# Sheet2.net
KiCad netlist of a schematic drawn in Altium Designer
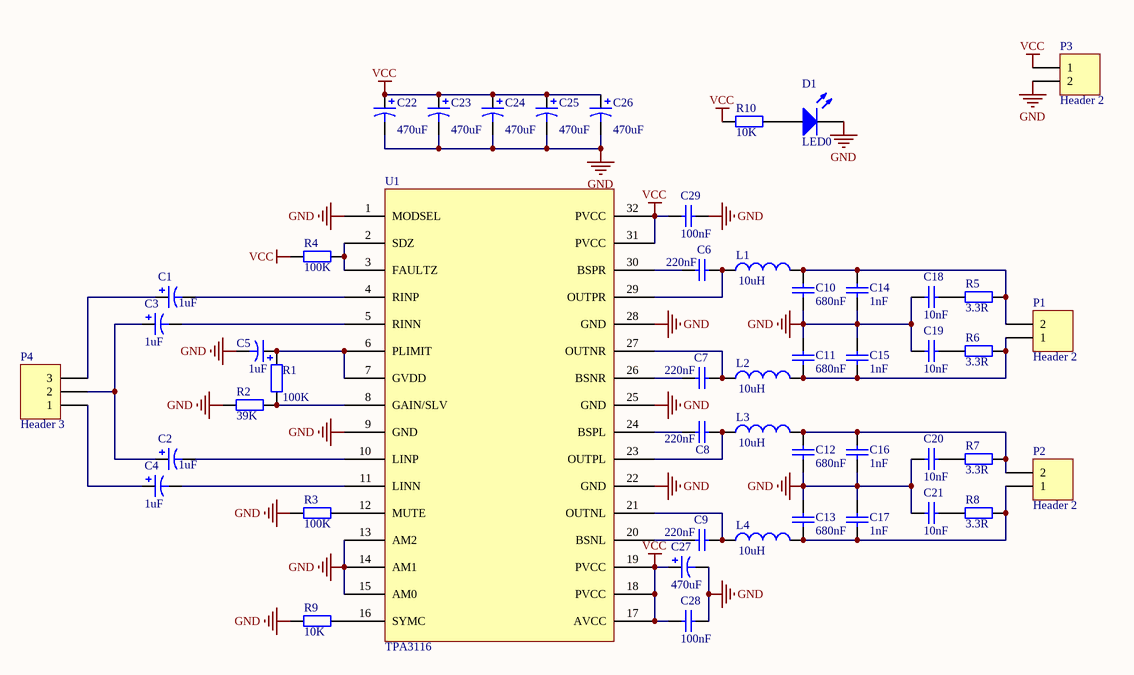
[diagram p0: Sheet2.SchDoc]

(export (version "E")
  (design (tool "Eeschema 10.0.6"))
  (components
    (comp (ref "C1")
      (value "1uF")
      (footprint "C0603")
      (description "Polarized Capacitor (Radial)")
      (fields (field (name "Comment") "Cap Pol1") (field (name "PUBLISHER") "Altium Limited"))
      (libsource (lib "Miscellaneous Devices") (part "Cap Pol1"))
    )
    (comp (ref "C2")
      (value "1uF")
      (footprint "C0603")
      (description "Polarized Capacitor (Radial)")
      (fields (field (name "Comment") "Cap Pol1") (field (name "PUBLISHER") "Altium Limited"))
      (libsource (lib "Miscellaneous Devices") (part "Cap Pol1"))
    )
    (comp (ref "C3")
      (value "1uF")
      (footprint "C0603")
      (description "Polarized Capacitor (Radial)")
      (fields (field (name "Comment") "Cap Pol1") (field (name "PUBLISHER") "Altium Limited"))
      (libsource (lib "Miscellaneous Devices") (part "Cap Pol1"))
    )
    (comp (ref "C4")
      (value "1uF")
      (footprint "C0603")
      (description "Polarized Capacitor (Radial)")
      (fields (field (name "Comment") "Cap Pol1") (field (name "PUBLISHER") "Altium Limited"))
      (libsource (lib "Miscellaneous Devices") (part "Cap Pol1"))
    )
    (comp (ref "C5")
      (value "1uF")
      (footprint "C0603")
      (description "Polarized Capacitor (Radial)")
      (fields (field (name "Comment") "Cap Pol1") (field (name "PUBLISHER") "Altium Limited"))
      (libsource (lib "Miscellaneous Devices") (part "Cap Pol1"))
    )
    (comp (ref "C6")
      (value "220nF")
      (footprint "C0805")
      (description "Capacitor")
      (fields (field (name "Comment") "Cap") (field (name "PUBLISHER") "Altium Limited"))
      (libsource (lib "Miscellaneous Devices") (part "Cap"))
    )
    (comp (ref "C7")
      (value "220nF")
      (footprint "C0805")
      (description "Capacitor")
      (fields (field (name "Comment") "Cap") (field (name "PUBLISHER") "Altium Limited"))
      (libsource (lib "Miscellaneous Devices") (part "Cap"))
    )
    (comp (ref "C8")
      (value "220nF")
      (footprint "C0805")
      (description "Capacitor")
      (fields (field (name "Comment") "Cap") (field (name "PUBLISHER") "Altium Limited"))
      (libsource (lib "Miscellaneous Devices") (part "Cap"))
    )
    (comp (ref "C9")
      (value "220nF")
      (footprint "C0805")
      (description "Capacitor")
      (fields (field (name "Comment") "Cap") (field (name "PUBLISHER") "Altium Limited"))
      (libsource (lib "Miscellaneous Devices") (part "Cap"))
    )
    (comp (ref "C10")
      (value "680nF")
      (footprint "C0805")
      (description "Capacitor")
      (fields (field (name "Comment") "Cap") (field (name "PUBLISHER") "Altium Limited"))
      (libsource (lib "Miscellaneous Devices") (part "Cap"))
    )
    (comp (ref "C11")
      (value "680nF")
      (footprint "C0805")
      (description "Capacitor")
      (fields (field (name "Comment") "Cap") (field (name "PUBLISHER") "Altium Limited"))
      (libsource (lib "Miscellaneous Devices") (part "Cap"))
    )
    (comp (ref "C12")
      (value "680nF")
      (footprint "C0805")
      (description "Capacitor")
      (fields (field (name "Comment") "Cap") (field (name "PUBLISHER") "Altium Limited"))
      (libsource (lib "Miscellaneous Devices") (part "Cap"))
    )
    (comp (ref "C13")
      (value "680nF")
      (footprint "C0805")
      (description "Capacitor")
      (fields (field (name "Comment") "Cap") (field (name "PUBLISHER") "Altium Limited"))
      (libsource (lib "Miscellaneous Devices") (part "Cap"))
    )
    (comp (ref "C14")
      (value "1nF")
      (footprint "C0603")
      (description "Capacitor")
      (fields (field (name "Comment") "Cap") (field (name "PUBLISHER") "Altium Limited"))
      (libsource (lib "Miscellaneous Devices") (part "Cap"))
    )
    (comp (ref "C15")
      (value "1nF")
      (footprint "C0603")
      (description "Capacitor")
      (fields (field (name "Comment") "Cap") (field (name "PUBLISHER") "Altium Limited"))
      (libsource (lib "Miscellaneous Devices") (part "Cap"))
    )
    (comp (ref "C16")
      (value "1nF")
      (footprint "C0603")
      (description "Capacitor")
      (fields (field (name "Comment") "Cap") (field (name "PUBLISHER") "Altium Limited"))
      (libsource (lib "Miscellaneous Devices") (part "Cap"))
    )
    (comp (ref "C17")
      (value "1nF")
      (footprint "C0603")
      (description "Capacitor")
      (fields (field (name "Comment") "Cap") (field (name "PUBLISHER") "Altium Limited"))
      (libsource (lib "Miscellaneous Devices") (part "Cap"))
    )
    (comp (ref "C18")
      (value "10nF")
      (footprint "C0603")
      (description "Capacitor")
      (fields (field (name "Comment") "Cap") (field (name "PUBLISHER") "Altium Limited"))
      (libsource (lib "Miscellaneous Devices") (part "Cap"))
    )
    (comp (ref "C19")
      (value "10nF")
      (footprint "C0603")
      (description "Capacitor")
      (fields (field (name "Comment") "Cap") (field (name "PUBLISHER") "Altium Limited"))
      (libsource (lib "Miscellaneous Devices") (part "Cap"))
    )
    (comp (ref "C20")
      (value "10nF")
      (footprint "C0603")
      (description "Capacitor")
      (fields (field (name "Comment") "Cap") (field (name "PUBLISHER") "Altium Limited"))
      (libsource (lib "Miscellaneous Devices") (part "Cap"))
    )
    (comp (ref "C21")
      (value "10nF")
      (footprint "C0603")
      (description "Capacitor")
      (fields (field (name "Comment") "Cap") (field (name "PUBLISHER") "Altium Limited"))
      (libsource (lib "Miscellaneous Devices") (part "Cap"))
    )
    (comp (ref "C22")
      (value "470uF")
      (footprint "EC-470/25")
      (description "Polarized Capacitor (Radial)")
      (fields (field (name "Comment") "Cap Pol1") (field (name "PUBLISHER") "Altium Limited"))
      (libsource (lib "Miscellaneous Devices") (part "Cap Pol1"))
    )
    (comp (ref "C23")
      (value "470uF")
      (footprint "EC-470/25")
      (description "Polarized Capacitor (Radial)")
      (fields (field (name "Comment") "Cap Pol1") (field (name "PUBLISHER") "Altium Limited"))
      (libsource (lib "Miscellaneous Devices") (part "Cap Pol1"))
    )
    (comp (ref "C24")
      (value "470uF")
      (footprint "EC-470/25")
      (description "Polarized Capacitor (Radial)")
      (fields (field (name "Comment") "Cap Pol1") (field (name "PUBLISHER") "Altium Limited"))
      (libsource (lib "Miscellaneous Devices") (part "Cap Pol1"))
    )
    (comp (ref "C25")
      (value "470uF")
      (footprint "EC-470/25")
      (description "Polarized Capacitor (Radial)")
      (fields (field (name "Comment") "Cap Pol1") (field (name "PUBLISHER") "Altium Limited"))
      (libsource (lib "Miscellaneous Devices") (part "Cap Pol1"))
    )
    (comp (ref "C26")
      (value "470uF")
      (footprint "EC-470/25")
      (description "Polarized Capacitor (Radial)")
      (fields (field (name "Comment") "Cap Pol1") (field (name "PUBLISHER") "Altium Limited"))
      (libsource (lib "Miscellaneous Devices") (part "Cap Pol1"))
    )
    (comp (ref "C27")
      (value "470uF")
      (footprint "EC-470/25")
      (description "Polarized Capacitor (Radial)")
      (fields (field (name "Comment") "Cap Pol1") (field (name "PUBLISHER") "Altium Limited"))
      (libsource (lib "Miscellaneous Devices") (part "Cap Pol1"))
    )
    (comp (ref "C28")
      (value "100nF")
      (footprint "C0603")
      (description "Capacitor")
      (fields (field (name "Comment") "Cap") (field (name "PUBLISHER") "Altium Limited"))
      (libsource (lib "Miscellaneous Devices") (part "Cap"))
    )
    (comp (ref "C29")
      (value "100nF")
      (footprint "C0603")
      (description "Capacitor")
      (fields (field (name "Comment") "Cap") (field (name "PUBLISHER") "Altium Limited"))
      (libsource (lib "Miscellaneous Devices") (part "Cap"))
    )
    (comp (ref "D1")
      (value "LED0")
      (footprint "D0805")
      (description "Typical INFRARED GaAs LED")
      (fields (field (name "PUBLISHER") "Altium Limited"))
      (libsource (lib "Miscellaneous Devices") (part "LED0"))
    )
    (comp (ref "L1")
      (value "10uH")
      (footprint "L-12*12mm-S")
      (description "Inductor")
      (fields (field (name "PUBLISHER") "Altium Limited"))
      (libsource (lib "Miscellaneous Devices") (part "Inductor"))
    )
    (comp (ref "L2")
      (value "10uH")
      (footprint "L-12*12mm-S")
      (description "Inductor")
      (fields (field (name "PUBLISHER") "Altium Limited"))
      (libsource (lib "Miscellaneous Devices") (part "Inductor"))
    )
    (comp (ref "L3")
      (value "10uH")
      (footprint "L-12*12mm-S")
      (description "Inductor")
      (fields (field (name "PUBLISHER") "Altium Limited"))
      (libsource (lib "Miscellaneous Devices") (part "Inductor"))
    )
    (comp (ref "L4")
      (value "10uH")
      (footprint "L-12*12mm-S")
      (description "Inductor")
      (fields (field (name "PUBLISHER") "Altium Limited"))
      (libsource (lib "Miscellaneous Devices") (part "Inductor"))
    )
    (comp (ref "P1")
      (value "Header 2")
      (footprint "HX5.08-2")
      (description "Header, 2-Pin")
      (fields (field (name "PUBLISHER") "Altium Limited"))
      (libsource (lib "Miscellaneous Connectors") (part "Header 2"))
    )
    (comp (ref "P2")
      (value "Header 2")
      (footprint "HX5.08-2")
      (description "Header, 2-Pin")
      (fields (field (name "PUBLISHER") "Altium Limited"))
      (libsource (lib "Miscellaneous Connectors") (part "Header 2"))
    )
    (comp (ref "P3")
      (value "Header 2")
      (footprint "HX5.08-2")
      (description "Header, 2-Pin")
      (fields (field (name "PUBLISHER") "Altium Limited"))
      (libsource (lib "") (part "Header 2_1"))
    )
    (comp (ref "P4")
      (value "Header 3")
      (footprint "HX2.54-3")
      (description "Header, 3-Pin")
      (fields (field (name "PUBLISHER") "Altium Limited"))
      (libsource (lib "Miscellaneous Connectors") (part "Header 3"))
    )
    (comp (ref "R1")
      (value "100K")
      (footprint "R0603")
      (description "Resistor")
      (fields (field (name "Comment") "Res2") (field (name "PUBLISHER") "Altium Limited"))
      (libsource (lib "") (part "Res2_2"))
    )
    (comp (ref "R2")
      (value "39K")
      (footprint "R0603")
      (description "Resistor")
      (fields (field (name "Comment") "Res2") (field (name "PUBLISHER") "Altium Limited"))
      (libsource (lib "") (part "Res2_1"))
    )
    (comp (ref "R3")
      (value "100K")
      (footprint "R0603")
      (description "Resistor")
      (fields (field (name "Comment") "Res2") (field (name "PUBLISHER") "Altium Limited"))
      (libsource (lib "Miscellaneous Devices") (part "Res2"))
    )
    (comp (ref "R4")
      (value "100K")
      (footprint "R0603")
      (description "Resistor")
      (fields (field (name "Comment") "Res2") (field (name "PUBLISHER") "Altium Limited"))
      (libsource (lib "") (part "Res2_1"))
    )
    (comp (ref "R5")
      (value "3.3R")
      (footprint "R0603")
      (description "Resistor")
      (fields (field (name "Comment") "Res2") (field (name "PUBLISHER") "Altium Limited"))
      (libsource (lib "Miscellaneous Devices") (part "Res2"))
    )
    (comp (ref "R6")
      (value "3.3R")
      (footprint "R0603")
      (description "Resistor")
      (fields (field (name "Comment") "Res2") (field (name "PUBLISHER") "Altium Limited"))
      (libsource (lib "Miscellaneous Devices") (part "Res2"))
    )
    (comp (ref "R7")
      (value "3.3R")
      (footprint "R0603")
      (description "Resistor")
      (fields (field (name "Comment") "Res2") (field (name "PUBLISHER") "Altium Limited"))
      (libsource (lib "") (part "Res2_1"))
    )
    (comp (ref "R8")
      (value "3.3R")
      (footprint "R0603")
      (description "Resistor")
      (fields (field (name "Comment") "Res2") (field (name "PUBLISHER") "Altium Limited"))
      (libsource (lib "") (part "Res2_1"))
    )
    (comp (ref "R9")
      (value "10K")
      (footprint "R0603")
      (description "Resistor")
      (fields (field (name "Comment") "Res2") (field (name "PUBLISHER") "Altium Limited"))
      (libsource (lib "Miscellaneous Devices") (part "Res2"))
    )
    (comp (ref "R10")
      (value "10K")
      (footprint "R0603")
      (description "Resistor")
      (fields (field (name "Comment") "Res2") (field (name "PUBLISHER") "Altium Limited"))
      (libsource (lib "Miscellaneous Devices") (part "Res2"))
    )
    (comp (ref "U1") (value "TPA3116") (footprint "HTSSOP32") (libsource (lib "MySCHLib") (part "TPA3116")))
  )
  (nets
    (net (code "1") (name "GND") (class "Default")
      (node (ref "C10") (pin "1") (pinfunction "1_1") (pintype "passive"))
      (node (ref "C11") (pin "2") (pinfunction "2_2") (pintype "passive"))
      (node (ref "C12") (pin "1") (pinfunction "1_1") (pintype "passive"))
      (node (ref "C13") (pin "2") (pinfunction "2_2") (pintype "passive"))
      (node (ref "C14") (pin "1") (pinfunction "1_1") (pintype "passive"))
      (node (ref "C15") (pin "2") (pinfunction "2_2") (pintype "passive"))
      (node (ref "C16") (pin "1") (pinfunction "1_1") (pintype "passive"))
      (node (ref "C17") (pin "2") (pinfunction "2_2") (pintype "passive"))
      (node (ref "C18") (pin "2") (pinfunction "2_2") (pintype "passive"))
      (node (ref "C19") (pin "2") (pinfunction "2_2") (pintype "passive"))
      (node (ref "C20") (pin "1") (pinfunction "1_1") (pintype "passive"))
      (node (ref "C21") (pin "1") (pinfunction "1_1") (pintype "passive"))
      (node (ref "C22") (pin "2") (pinfunction "2_2") (pintype "passive"))
      (node (ref "C23") (pin "2") (pinfunction "2_2") (pintype "passive"))
      (node (ref "C24") (pin "2") (pinfunction "2_2") (pintype "passive"))
      (node (ref "C25") (pin "2") (pinfunction "2_2") (pintype "passive"))
      (node (ref "C26") (pin "2") (pinfunction "2_2") (pintype "passive"))
      (node (ref "C27") (pin "2") (pinfunction "2_2") (pintype "passive"))
      (node (ref "C28") (pin "1") (pinfunction "1_1") (pintype "passive"))
      (node (ref "C29") (pin "1") (pinfunction "1_1") (pintype "passive"))
      (node (ref "C5") (pin "2") (pinfunction "2_2") (pintype "passive"))
      (node (ref "D1") (pin "2") (pinfunction "K_2") (pintype "passive"))
      (node (ref "P3") (pin "2") (pinfunction "2_2") (pintype "passive"))
      (node (ref "R2") (pin "2") (pinfunction "2_2") (pintype "passive"))
      (node (ref "R3") (pin "1") (pinfunction "1_1") (pintype "passive"))
      (node (ref "R9") (pin "1") (pinfunction "1_1") (pintype "passive"))
      (node (ref "U1") (pin "1") (pinfunction "MODSEL_1") (pintype "passive"))
      (node (ref "U1") (pin "13") (pinfunction "AM2_13") (pintype "passive"))
      (node (ref "U1") (pin "14") (pinfunction "AM1_14") (pintype "passive"))
      (node (ref "U1") (pin "15") (pinfunction "AM0_15") (pintype "passive"))
      (node (ref "U1") (pin "22") (pinfunction "GND_22") (pintype "passive"))
      (node (ref "U1") (pin "25") (pinfunction "GND_25") (pintype "passive"))
      (node (ref "U1") (pin "28") (pinfunction "GND_28") (pintype "passive"))
      (node (ref "U1") (pin "9") (pinfunction "GND_9") (pintype "passive"))
    )
    (net (code "2") (name "Net-(C1-Pad1)") (class "Default")
      (node (ref "C1") (pin "1") (pinfunction "1_1") (pintype "passive"))
      (node (ref "P4") (pin "3") (pinfunction "3_3") (pintype "passive"))
    )
    (net (code "3") (name "Net-(C2-Pad1)") (class "Default")
      (node (ref "C2") (pin "1") (pinfunction "1_1") (pintype "passive"))
      (node (ref "C3") (pin "1") (pinfunction "1_1") (pintype "passive"))
      (node (ref "P4") (pin "2") (pinfunction "2_2") (pintype "passive"))
    )
    (net (code "4") (name "Net-(C4-Pad1)") (class "Default")
      (node (ref "C4") (pin "1") (pinfunction "1_1") (pintype "passive"))
      (node (ref "P4") (pin "1") (pinfunction "1_1") (pintype "passive"))
    )
    (net (code "5") (name "Net-(C10-Pad2)") (class "Default")
      (node (ref "C10") (pin "2") (pinfunction "2_2") (pintype "passive"))
      (node (ref "C14") (pin "2") (pinfunction "2_2") (pintype "passive"))
      (node (ref "L1") (pin "2") (pinfunction "2_2") (pintype "passive"))
      (node (ref "P1") (pin "2") (pinfunction "2_2") (pintype "passive"))
      (node (ref "R5") (pin "2") (pinfunction "2_2") (pintype "passive"))
    )
    (net (code "6") (name "Net-(C11-Pad1)") (class "Default")
      (node (ref "C11") (pin "1") (pinfunction "1_1") (pintype "passive"))
      (node (ref "C15") (pin "1") (pinfunction "1_1") (pintype "passive"))
      (node (ref "L2") (pin "2") (pinfunction "2_2") (pintype "passive"))
      (node (ref "P1") (pin "1") (pinfunction "1_1") (pintype "passive"))
      (node (ref "R6") (pin "2") (pinfunction "2_2") (pintype "passive"))
    )
    (net (code "7") (name "Net-(C12-Pad2)") (class "Default")
      (node (ref "C12") (pin "2") (pinfunction "2_2") (pintype "passive"))
      (node (ref "C16") (pin "2") (pinfunction "2_2") (pintype "passive"))
      (node (ref "L3") (pin "2") (pinfunction "2_2") (pintype "passive"))
      (node (ref "P2") (pin "2") (pinfunction "2_2") (pintype "passive"))
      (node (ref "R7") (pin "1") (pinfunction "1_1") (pintype "passive"))
    )
    (net (code "8") (name "Net-(C13-Pad1)") (class "Default")
      (node (ref "C13") (pin "1") (pinfunction "1_1") (pintype "passive"))
      (node (ref "C17") (pin "1") (pinfunction "1_1") (pintype "passive"))
      (node (ref "L4") (pin "2") (pinfunction "2_2") (pintype "passive"))
      (node (ref "P2") (pin "1") (pinfunction "1_1") (pintype "passive"))
      (node (ref "R8") (pin "1") (pinfunction "1_1") (pintype "passive"))
    )
    (net (code "9") (name "Net-(C18-Pad1)") (class "Default")
      (node (ref "C18") (pin "1") (pinfunction "1_1") (pintype "passive"))
      (node (ref "R5") (pin "1") (pinfunction "1_1") (pintype "passive"))
    )
    (net (code "10") (name "Net-(C19-Pad1)") (class "Default")
      (node (ref "C19") (pin "1") (pinfunction "1_1") (pintype "passive"))
      (node (ref "R6") (pin "1") (pinfunction "1_1") (pintype "passive"))
    )
    (net (code "11") (name "Net-(C20-Pad2)") (class "Default")
      (node (ref "C20") (pin "2") (pinfunction "2_2") (pintype "passive"))
      (node (ref "R7") (pin "2") (pinfunction "2_2") (pintype "passive"))
    )
    (net (code "12") (name "Net-(C21-Pad2)") (class "Default")
      (node (ref "C21") (pin "2") (pinfunction "2_2") (pintype "passive"))
      (node (ref "R8") (pin "2") (pinfunction "2_2") (pintype "passive"))
    )
    (net (code "13") (name "Net-(D1-A)") (class "Default")
      (node (ref "D1") (pin "1") (pinfunction "A_1") (pintype "passive"))
      (node (ref "R10") (pin "2") (pinfunction "2_2") (pintype "passive"))
    )
    (net (code "14") (name "Net-(U1-BSNL)") (class "Default")
      (node (ref "C9") (pin "1") (pinfunction "1_1") (pintype "passive"))
      (node (ref "U1") (pin "20") (pinfunction "BSNL_20") (pintype "passive"))
    )
    (net (code "15") (name "Net-(U1-BSNR)") (class "Default")
      (node (ref "C7") (pin "1") (pinfunction "1_1") (pintype "passive"))
      (node (ref "U1") (pin "26") (pinfunction "BSNR_26") (pintype "passive"))
    )
    (net (code "16") (name "Net-(U1-BSPL)") (class "Default")
      (node (ref "C8") (pin "1") (pinfunction "1_1") (pintype "passive"))
      (node (ref "U1") (pin "24") (pinfunction "BSPL_24") (pintype "passive"))
    )
    (net (code "17") (name "Net-(U1-BSPR)") (class "Default")
      (node (ref "C6") (pin "1") (pinfunction "1_1") (pintype "passive"))
      (node (ref "U1") (pin "30") (pinfunction "BSPR_30") (pintype "passive"))
    )
    (net (code "18") (name "Net-(U1-FAULTZ)") (class "Default")
      (node (ref "R4") (pin "1") (pinfunction "1_1") (pintype "passive"))
      (node (ref "U1") (pin "2") (pinfunction "SDZ_2") (pintype "passive"))
      (node (ref "U1") (pin "3") (pinfunction "FAULTZ_3") (pintype "passive"))
    )
    (net (code "19") (name "Net-(U1-GAIN{slash}SLV)") (class "Default")
      (node (ref "R1") (pin "1") (pinfunction "1_1") (pintype "passive"))
      (node (ref "R2") (pin "1") (pinfunction "1_1") (pintype "passive"))
      (node (ref "U1") (pin "8") (pinfunction "GAIN/SLV_8") (pintype "passive"))
    )
    (net (code "20") (name "Net-(U1-GVDD)") (class "Default")
      (node (ref "C5") (pin "1") (pinfunction "1_1") (pintype "passive"))
      (node (ref "R1") (pin "2") (pinfunction "2_2") (pintype "passive"))
      (node (ref "U1") (pin "6") (pinfunction "PLIMIT_6") (pintype "passive"))
      (node (ref "U1") (pin "7") (pinfunction "GVDD_7") (pintype "passive"))
    )
    (net (code "21") (name "Net-(U1-LINN)") (class "Default")
      (node (ref "C4") (pin "2") (pinfunction "2_2") (pintype "passive"))
      (node (ref "U1") (pin "11") (pinfunction "LINN_11") (pintype "passive"))
    )
    (net (code "22") (name "Net-(U1-LINP)") (class "Default")
      (node (ref "C2") (pin "2") (pinfunction "2_2") (pintype "passive"))
      (node (ref "U1") (pin "10") (pinfunction "LINP_10") (pintype "passive"))
    )
    (net (code "23") (name "Net-(U1-MUTE)") (class "Default")
      (node (ref "R3") (pin "2") (pinfunction "2_2") (pintype "passive"))
      (node (ref "U1") (pin "12") (pinfunction "MUTE_12") (pintype "passive"))
    )
    (net (code "24") (name "Net-(U1-OUTNL)") (class "Default")
      (node (ref "C9") (pin "2") (pinfunction "2_2") (pintype "passive"))
      (node (ref "L4") (pin "1") (pinfunction "1_1") (pintype "passive"))
      (node (ref "U1") (pin "21") (pinfunction "OUTNL_21") (pintype "passive"))
    )
    (net (code "25") (name "Net-(U1-OUTNR)") (class "Default")
      (node (ref "C7") (pin "2") (pinfunction "2_2") (pintype "passive"))
      (node (ref "L2") (pin "1") (pinfunction "1_1") (pintype "passive"))
      (node (ref "U1") (pin "27") (pinfunction "OUTNR_27") (pintype "passive"))
    )
    (net (code "26") (name "Net-(U1-OUTPL)") (class "Default")
      (node (ref "C8") (pin "2") (pinfunction "2_2") (pintype "passive"))
      (node (ref "L3") (pin "1") (pinfunction "1_1") (pintype "passive"))
      (node (ref "U1") (pin "23") (pinfunction "OUTPL_23") (pintype "passive"))
    )
    (net (code "27") (name "Net-(U1-OUTPR)") (class "Default")
      (node (ref "C6") (pin "2") (pinfunction "2_2") (pintype "passive"))
      (node (ref "L1") (pin "1") (pinfunction "1_1") (pintype "passive"))
      (node (ref "U1") (pin "29") (pinfunction "OUTPR_29") (pintype "passive"))
    )
    (net (code "28") (name "Net-(U1-RINN)") (class "Default")
      (node (ref "C3") (pin "2") (pinfunction "2_2") (pintype "passive"))
      (node (ref "U1") (pin "5") (pinfunction "RINN_5") (pintype "passive"))
    )
    (net (code "29") (name "Net-(U1-RINP)") (class "Default")
      (node (ref "C1") (pin "2") (pinfunction "2_2") (pintype "passive"))
      (node (ref "U1") (pin "4") (pinfunction "RINP_4") (pintype "passive"))
    )
    (net (code "30") (name "Net-(U1-SYMC)") (class "Default")
      (node (ref "R9") (pin "2") (pinfunction "2_2") (pintype "passive"))
      (node (ref "U1") (pin "16") (pinfunction "SYMC_16") (pintype "passive"))
    )
    (net (code "31") (name "VCC") (class "Default")
      (node (ref "C22") (pin "1") (pinfunction "1_1") (pintype "passive"))
      (node (ref "C23") (pin "1") (pinfunction "1_1") (pintype "passive"))
      (node (ref "C24") (pin "1") (pinfunction "1_1") (pintype "passive"))
      (node (ref "C25") (pin "1") (pinfunction "1_1") (pintype "passive"))
      (node (ref "C26") (pin "1") (pinfunction "1_1") (pintype "passive"))
      (node (ref "C27") (pin "1") (pinfunction "1_1") (pintype "passive"))
      (node (ref "C28") (pin "2") (pinfunction "2_2") (pintype "passive"))
      (node (ref "C29") (pin "2") (pinfunction "2_2") (pintype "passive"))
      (node (ref "P3") (pin "1") (pinfunction "1_1") (pintype "passive"))
      (node (ref "R10") (pin "1") (pinfunction "1_1") (pintype "passive"))
      (node (ref "R4") (pin "2") (pinfunction "2_2") (pintype "passive"))
      (node (ref "U1") (pin "17") (pinfunction "AVCC_17") (pintype "passive"))
      (node (ref "U1") (pin "18") (pinfunction "PVCC_18") (pintype "passive"))
      (node (ref "U1") (pin "19") (pinfunction "PVCC_19") (pintype "passive"))
      (node (ref "U1") (pin "31") (pinfunction "PVCC_31") (pintype "passive"))
      (node (ref "U1") (pin "32") (pinfunction "PVCC_32") (pintype "passive"))
    )
  )
)
